# IOX16_v22.net
KiCad netlist of a schematic drawn in EAGLE
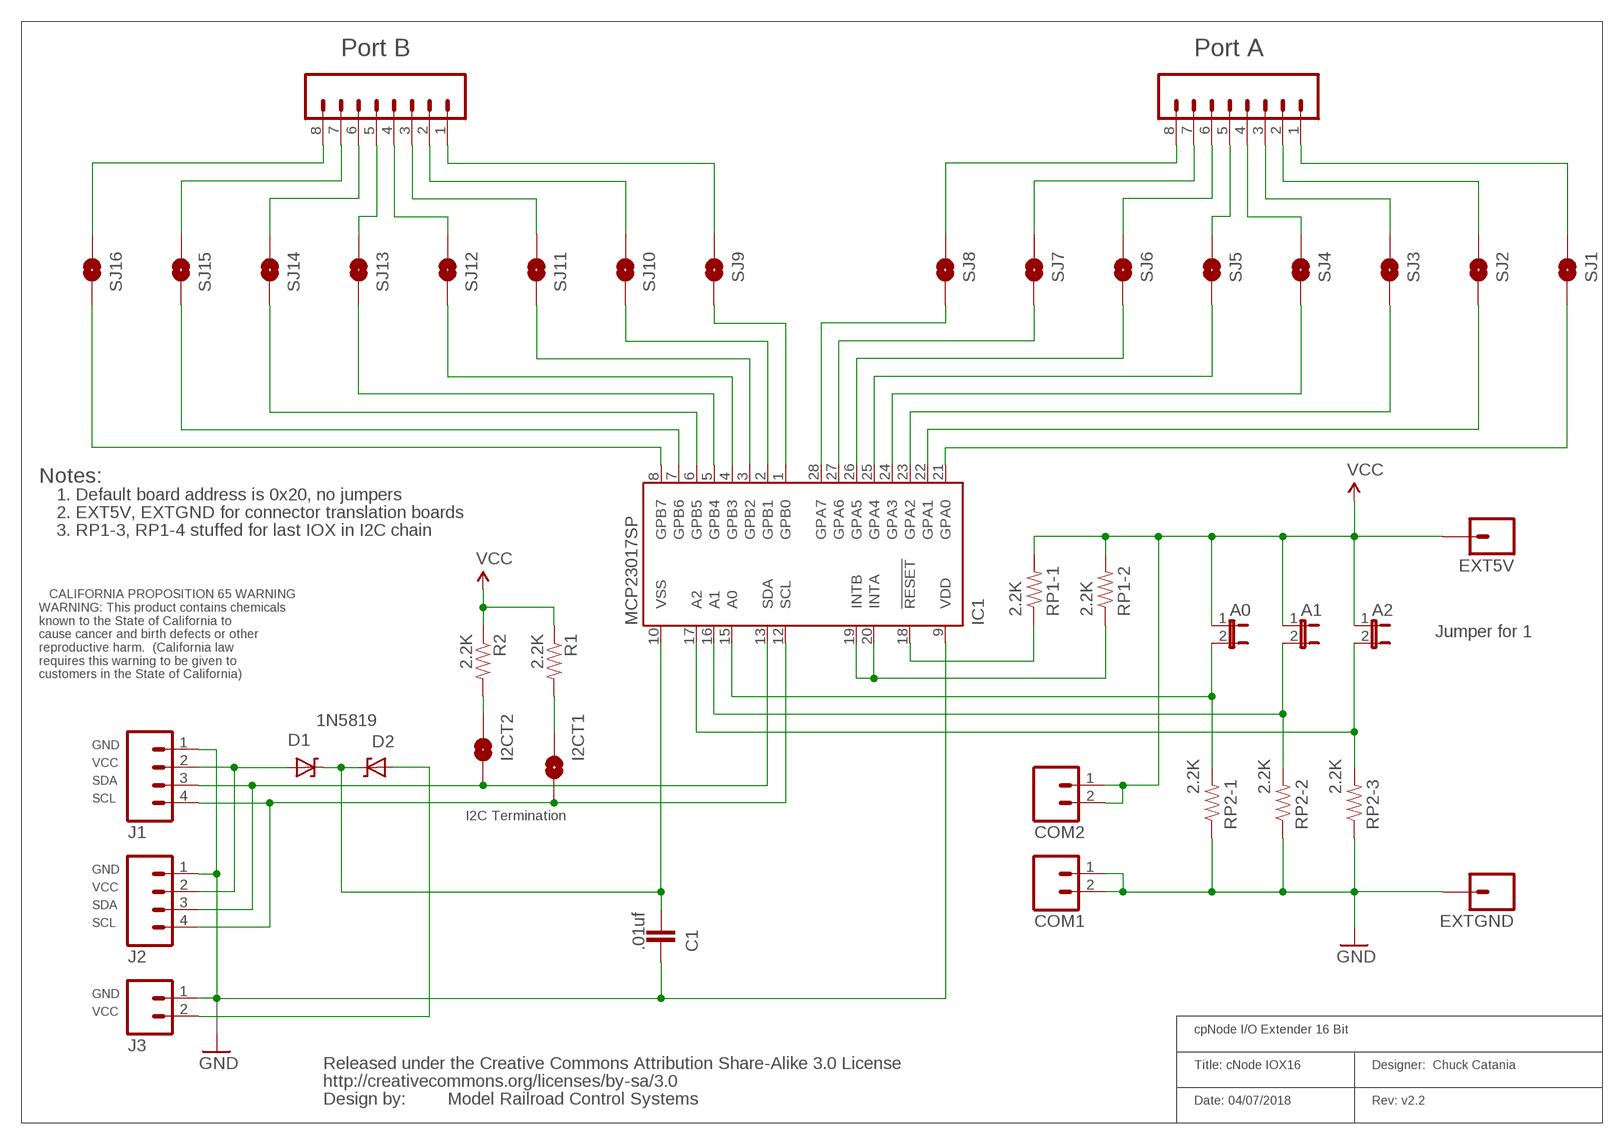
[diagram p0: schematic, sheet 1]

(export (version "E")
  (design (tool "Eeschema 10.0.6"))
  (components
    (comp (ref "A0")
      (value "JUMPER-2PTH")
      (footprint "eagle-import:1X02")
      (libsource (lib "eagle-import") (part "JUMPER-2PTH"))
    )
    (comp (ref "A1")
      (value "JUMPER-2PTH")
      (footprint "eagle-import:1X02")
      (libsource (lib "eagle-import") (part "JUMPER-2PTH"))
    )
    (comp (ref "A2")
      (value "JUMPER-2PTH")
      (footprint "eagle-import:1X02")
      (libsource (lib "eagle-import") (part "JUMPER-2PTH"))
    )
    (comp (ref "C1")
      (value ".01uf")
      (footprint "eagle-import:AXIAL-5MM")
      (libsource (lib "eagle-import") (part "CAP_"))
    )
    (comp (ref "COM1")
      (value "M021X02_NO_SILK")
      (footprint "eagle-import:1X02_NO_SILK")
      (libsource (lib "eagle-import") (part "M021X02_NO_SILK"))
    )
    (comp (ref "COM2")
      (value "M021X02_NO_SILK")
      (footprint "eagle-import:1X02_NO_SILK")
      (libsource (lib "eagle-import") (part "M021X02_NO_SILK"))
    )
    (comp (ref "D1")
      (value "DIODE-ZENERPTH")
      (footprint "eagle-import:DIODE-ZENER")
      (libsource (lib "eagle-import") (part "DIODE-ZENERPTH"))
    )
    (comp (ref "D2")
      (value "DIODE-ZENERPTH")
      (footprint "eagle-import:DIODE-ZENER")
      (libsource (lib "eagle-import") (part "DIODE-ZENERPTH"))
    )
    (comp (ref "EXT5V")
      (value "M01PTH_LONGPAD")
      (footprint "eagle-import:1X01_LONGPAD")
      (libsource (lib "eagle-import") (part "M01PTH_LONGPAD"))
    )
    (comp (ref "EXTGND")
      (value "M01PTH_LONGPAD")
      (footprint "eagle-import:1X01_LONGPAD")
      (libsource (lib "eagle-import") (part "M01PTH_LONGPAD"))
    )
    (comp (ref "I2CT1")
      (value "PAD-SOLDERJUMPERNC")
      (footprint "eagle-import:2P-SMD-2X3.3")
      (libsource (lib "eagle-import") (part "PAD-SOLDERJUMPERNC"))
    )
    (comp (ref "I2CT2")
      (value "PAD-SOLDERJUMPERNC")
      (footprint "eagle-import:2P-SMD-2X3.3")
      (libsource (lib "eagle-import") (part "PAD-SOLDERJUMPERNC"))
    )
    (comp (ref "IC1")
      (value "MCP23017SP")
      (footprint "eagle-import:DIL28-3")
      (fields (field (name "MF") "MICROCHIP") (field (name "MPN") "MCP23017-E/SP"))
      (libsource (lib "eagle-import") (part "MCP23017SP"))
    )
    (comp (ref "J1")
      (value "M04PTH")
      (footprint "eagle-import:1X04")
      (libsource (lib "eagle-import") (part "M04PTH"))
    )
    (comp (ref "J2")
      (value "M04PTH")
      (footprint "eagle-import:1X04")
      (libsource (lib "eagle-import") (part "M04PTH"))
    )
    (comp (ref "J3")
      (value "M021X02_NO_SILK")
      (footprint "eagle-import:1X02_NO_SILK")
      (libsource (lib "eagle-import") (part "M021X02_NO_SILK"))
    )
    (comp (ref "PORTA")
      (value "M081X08")
      (footprint "eagle-import:1X08")
      (libsource (lib "eagle-import") (part "M081X08"))
    )
    (comp (ref "PORTB")
      (value "M081X08")
      (footprint "eagle-import:1X08")
      (libsource (lib "eagle-import") (part "M081X08"))
    )
    (comp (ref "R1")
      (value "2.2K")
      (footprint "eagle-import:AXIAL-0.4")
      (libsource (lib "eagle-import") (part "RESISTORPTH-1/4W"))
    )
    (comp (ref "R2")
      (value "2.2K")
      (footprint "eagle-import:AXIAL-0.4")
      (libsource (lib "eagle-import") (part "RESISTORPTH-1/4W"))
    )
    (comp (ref "RP1-1")
      (value "2.2K")
      (footprint "eagle-import:AXIAL-0.4")
      (libsource (lib "eagle-import") (part "RESISTORPTH-1/4W"))
    )
    (comp (ref "RP1-2")
      (value "2.2K")
      (footprint "eagle-import:AXIAL-0.4")
      (libsource (lib "eagle-import") (part "RESISTORPTH-1/4W"))
    )
    (comp (ref "RP2-1")
      (value "2.2K")
      (footprint "eagle-import:AXIAL-0.4")
      (libsource (lib "eagle-import") (part "RESISTORPTH-1/4W"))
    )
    (comp (ref "RP2-2")
      (value "2.2K")
      (footprint "eagle-import:AXIAL-0.4")
      (libsource (lib "eagle-import") (part "RESISTORPTH-1/4W"))
    )
    (comp (ref "RP2-3")
      (value "2.2K")
      (footprint "eagle-import:AXIAL-0.4")
      (libsource (lib "eagle-import") (part "RESISTORPTH-1/4W"))
    )
    (comp (ref "SJ1")
      (value "PAD-SOLDERJUMPERNC")
      (footprint "eagle-import:2P-SMD-2X3.3")
      (libsource (lib "eagle-import") (part "PAD-SOLDERJUMPERNC"))
    )
    (comp (ref "SJ2")
      (value "PAD-SOLDERJUMPERNC")
      (footprint "eagle-import:2P-SMD-2X3.3")
      (libsource (lib "eagle-import") (part "PAD-SOLDERJUMPERNC"))
    )
    (comp (ref "SJ3")
      (value "PAD-SOLDERJUMPERNC")
      (footprint "eagle-import:2P-SMD-2X3.3")
      (libsource (lib "eagle-import") (part "PAD-SOLDERJUMPERNC"))
    )
    (comp (ref "SJ4")
      (value "PAD-SOLDERJUMPERNC")
      (footprint "eagle-import:2P-SMD-2X3.3")
      (libsource (lib "eagle-import") (part "PAD-SOLDERJUMPERNC"))
    )
    (comp (ref "SJ5")
      (value "PAD-SOLDERJUMPERNC")
      (footprint "eagle-import:2P-SMD-2X3.3")
      (libsource (lib "eagle-import") (part "PAD-SOLDERJUMPERNC"))
    )
    (comp (ref "SJ6")
      (value "PAD-SOLDERJUMPERNC")
      (footprint "eagle-import:2P-SMD-2X3.3")
      (libsource (lib "eagle-import") (part "PAD-SOLDERJUMPERNC"))
    )
    (comp (ref "SJ7")
      (value "PAD-SOLDERJUMPERNC")
      (footprint "eagle-import:2P-SMD-2X3.3")
      (libsource (lib "eagle-import") (part "PAD-SOLDERJUMPERNC"))
    )
    (comp (ref "SJ8")
      (value "PAD-SOLDERJUMPERNC")
      (footprint "eagle-import:2P-SMD-2X3.3")
      (libsource (lib "eagle-import") (part "PAD-SOLDERJUMPERNC"))
    )
    (comp (ref "SJ9")
      (value "PAD-SOLDERJUMPERNC")
      (footprint "eagle-import:2P-SMD-2X3.3")
      (libsource (lib "eagle-import") (part "PAD-SOLDERJUMPERNC"))
    )
    (comp (ref "SJ10")
      (value "PAD-SOLDERJUMPERNC")
      (footprint "eagle-import:2P-SMD-2X3.3")
      (libsource (lib "eagle-import") (part "PAD-SOLDERJUMPERNC"))
    )
    (comp (ref "SJ11")
      (value "PAD-SOLDERJUMPERNC")
      (footprint "eagle-import:2P-SMD-2X3.3")
      (libsource (lib "eagle-import") (part "PAD-SOLDERJUMPERNC"))
    )
    (comp (ref "SJ12")
      (value "PAD-SOLDERJUMPERNC")
      (footprint "eagle-import:2P-SMD-2X3.3")
      (libsource (lib "eagle-import") (part "PAD-SOLDERJUMPERNC"))
    )
    (comp (ref "SJ13")
      (value "PAD-SOLDERJUMPERNC")
      (footprint "eagle-import:2P-SMD-2X3.3")
      (libsource (lib "eagle-import") (part "PAD-SOLDERJUMPERNC"))
    )
    (comp (ref "SJ14")
      (value "PAD-SOLDERJUMPERNC")
      (footprint "eagle-import:2P-SMD-2X3.3")
      (libsource (lib "eagle-import") (part "PAD-SOLDERJUMPERNC"))
    )
    (comp (ref "SJ15")
      (value "PAD-SOLDERJUMPERNC")
      (footprint "eagle-import:2P-SMD-2X3.3")
      (libsource (lib "eagle-import") (part "PAD-SOLDERJUMPERNC"))
    )
    (comp (ref "SJ16")
      (value "PAD-SOLDERJUMPERNC")
      (footprint "eagle-import:2P-SMD-2X3.3")
      (libsource (lib "eagle-import") (part "PAD-SOLDERJUMPERNC"))
    )
    (comp (ref "U$1")
      (value "CREATIVE_COMMONS")
      (footprint "eagle-import:CREATIVE_COMMONS")
      (libsource (lib "eagle-import") (part "CREATIVE_COMMONS"))
    )
    (comp (ref "U$2")
      (value "CA-PROP65WARNING")
      (footprint "eagle-import:CA-PROP65WARNING")
      (libsource (lib "eagle-import") (part "CA-PROP65WARNING"))
    )
  )
  (nets
    (net (code "1") (name "GND") (class "Default")
      (node (ref "COM1") (pin "1") (pinfunction "1_1") (pintype "passive"))
      (node (ref "COM1") (pin "2") (pinfunction "2_2") (pintype "passive"))
      (node (ref "EXTGND") (pin "1") (pinfunction "1_1") (pintype "passive"))
      (node (ref "RP2-1") (pin "P$1") (pinfunction "1_P$1") (pintype "passive"))
      (node (ref "RP2-2") (pin "P$1") (pinfunction "1_P$1") (pintype "passive"))
      (node (ref "RP2-3") (pin "P$1") (pinfunction "1_P$1") (pintype "passive"))
    )
    (net (code "2") (name "Net-(C1-1)") (class "Default")
      (node (ref "C1") (pin "P$1") (pinfunction "1_P$1") (pintype "passive"))
      (node (ref "IC1") (pin "9") (pinfunction "VDD_9") (pintype "power_in"))
      (node (ref "J1") (pin "1") (pinfunction "1_1") (pintype "passive"))
      (node (ref "J2") (pin "1") (pinfunction "1_1") (pintype "passive"))
      (node (ref "J3") (pin "1") (pinfunction "1_1") (pintype "passive"))
    )
    (net (code "3") (name "Net-(C1-2)") (class "Default")
      (node (ref "C1") (pin "P$2") (pinfunction "2_P$2") (pintype "passive"))
      (node (ref "D1") (pin "P$1") (pinfunction "C_P$1") (pintype "passive"))
      (node (ref "D2") (pin "P$1") (pinfunction "C_P$1") (pintype "passive"))
      (node (ref "IC1") (pin "10") (pinfunction "VSS_10") (pintype "power_in"))
    )
    (net (code "4") (name "Net-(D1-A)") (class "Default")
      (node (ref "D1") (pin "P$2") (pinfunction "A_P$2") (pintype "passive"))
      (node (ref "J1") (pin "2") (pinfunction "2_2") (pintype "passive"))
      (node (ref "J2") (pin "2") (pinfunction "2_2") (pintype "passive"))
    )
    (net (code "5") (name "Net-(D2-A)") (class "Default")
      (node (ref "D2") (pin "P$2") (pinfunction "A_P$2") (pintype "passive"))
      (node (ref "J3") (pin "2") (pinfunction "2_2") (pintype "passive"))
    )
    (net (code "6") (name "Net-(IC1-A0)") (class "Default")
      (node (ref "A0") (pin "2") (pinfunction "2_2") (pintype "passive"))
      (node (ref "IC1") (pin "15") (pinfunction "A0_15") (pintype "input"))
      (node (ref "RP2-1") (pin "P$2") (pinfunction "2_P$2") (pintype "passive"))
    )
    (net (code "7") (name "Net-(IC1-A1)") (class "Default")
      (node (ref "A1") (pin "2") (pinfunction "2_2") (pintype "passive"))
      (node (ref "IC1") (pin "16") (pinfunction "A1_16") (pintype "input"))
      (node (ref "RP2-2") (pin "P$2") (pinfunction "2_P$2") (pintype "passive"))
    )
    (net (code "8") (name "Net-(IC1-A2)") (class "Default")
      (node (ref "A2") (pin "2") (pinfunction "2_2") (pintype "passive"))
      (node (ref "IC1") (pin "17") (pinfunction "A2_17") (pintype "input"))
      (node (ref "RP2-3") (pin "P$2") (pinfunction "2_P$2") (pintype "passive"))
    )
    (net (code "9") (name "Net-(IC1-GPA0)") (class "Default")
      (node (ref "IC1") (pin "21") (pinfunction "GPA0_21") (pintype "bidirectional"))
      (node (ref "SJ1") (pin "2") (pinfunction "2_2") (pintype "passive"))
    )
    (net (code "10") (name "Net-(IC1-GPA1)") (class "Default")
      (node (ref "IC1") (pin "22") (pinfunction "GPA1_22") (pintype "bidirectional"))
      (node (ref "SJ2") (pin "2") (pinfunction "2_2") (pintype "passive"))
    )
    (net (code "11") (name "Net-(IC1-GPA2)") (class "Default")
      (node (ref "IC1") (pin "23") (pinfunction "GPA2_23") (pintype "bidirectional"))
      (node (ref "SJ3") (pin "2") (pinfunction "2_2") (pintype "passive"))
    )
    (net (code "12") (name "Net-(IC1-GPA3)") (class "Default")
      (node (ref "IC1") (pin "24") (pinfunction "GPA3_24") (pintype "bidirectional"))
      (node (ref "SJ4") (pin "2") (pinfunction "2_2") (pintype "passive"))
    )
    (net (code "13") (name "Net-(IC1-GPA4)") (class "Default")
      (node (ref "IC1") (pin "25") (pinfunction "GPA4_25") (pintype "bidirectional"))
      (node (ref "SJ5") (pin "2") (pinfunction "2_2") (pintype "passive"))
    )
    (net (code "14") (name "Net-(IC1-GPA5)") (class "Default")
      (node (ref "IC1") (pin "26") (pinfunction "GPA5_26") (pintype "bidirectional"))
      (node (ref "SJ6") (pin "2") (pinfunction "2_2") (pintype "passive"))
    )
    (net (code "15") (name "Net-(IC1-GPA6)") (class "Default")
      (node (ref "IC1") (pin "27") (pinfunction "GPA6_27") (pintype "bidirectional"))
      (node (ref "SJ7") (pin "2") (pinfunction "2_2") (pintype "passive"))
    )
    (net (code "16") (name "Net-(IC1-GPA7)") (class "Default")
      (node (ref "IC1") (pin "28") (pinfunction "GPA7_28") (pintype "bidirectional"))
      (node (ref "SJ8") (pin "2") (pinfunction "2_2") (pintype "passive"))
    )
    (net (code "17") (name "Net-(IC1-GPB0)") (class "Default")
      (node (ref "IC1") (pin "1") (pinfunction "GPB0_1") (pintype "bidirectional"))
      (node (ref "SJ9") (pin "2") (pinfunction "2_2") (pintype "passive"))
    )
    (net (code "18") (name "Net-(IC1-GPB1)") (class "Default")
      (node (ref "IC1") (pin "2") (pinfunction "GPB1_2") (pintype "bidirectional"))
      (node (ref "SJ10") (pin "2") (pinfunction "2_2") (pintype "passive"))
    )
    (net (code "19") (name "Net-(IC1-GPB2)") (class "Default")
      (node (ref "IC1") (pin "3") (pinfunction "GPB2_3") (pintype "bidirectional"))
      (node (ref "SJ11") (pin "2") (pinfunction "2_2") (pintype "passive"))
    )
    (net (code "20") (name "Net-(IC1-GPB3)") (class "Default")
      (node (ref "IC1") (pin "4") (pinfunction "GPB3_4") (pintype "bidirectional"))
      (node (ref "SJ12") (pin "2") (pinfunction "2_2") (pintype "passive"))
    )
    (net (code "21") (name "Net-(IC1-GPB4)") (class "Default")
      (node (ref "IC1") (pin "5") (pinfunction "GPB4_5") (pintype "bidirectional"))
      (node (ref "SJ13") (pin "2") (pinfunction "2_2") (pintype "passive"))
    )
    (net (code "22") (name "Net-(IC1-GPB5)") (class "Default")
      (node (ref "IC1") (pin "6") (pinfunction "GPB5_6") (pintype "bidirectional"))
      (node (ref "SJ14") (pin "2") (pinfunction "2_2") (pintype "passive"))
    )
    (net (code "23") (name "Net-(IC1-GPB6)") (class "Default")
      (node (ref "IC1") (pin "7") (pinfunction "GPB6_7") (pintype "bidirectional"))
      (node (ref "SJ15") (pin "2") (pinfunction "2_2") (pintype "passive"))
    )
    (net (code "24") (name "Net-(IC1-GPB7)") (class "Default")
      (node (ref "IC1") (pin "8") (pinfunction "GPB7_8") (pintype "bidirectional"))
      (node (ref "SJ16") (pin "2") (pinfunction "2_2") (pintype "passive"))
    )
    (net (code "25") (name "Net-(IC1-INTA)") (class "Default")
      (node (ref "IC1") (pin "19") (pinfunction "INTB_19") (pintype "output"))
      (node (ref "IC1") (pin "20") (pinfunction "INTA_20") (pintype "output"))
      (node (ref "RP1-2") (pin "P$1") (pinfunction "1_P$1") (pintype "passive"))
    )
    (net (code "26") (name "Net-(IC1-SCL)") (class "Default")
      (node (ref "I2CT1") (pin "2") (pinfunction "2_2") (pintype "passive"))
      (node (ref "IC1") (pin "12") (pinfunction "SCL_12") (pintype "input"))
      (node (ref "J1") (pin "4") (pinfunction "4_4") (pintype "passive"))
      (node (ref "J2") (pin "4") (pinfunction "4_4") (pintype "passive"))
    )
    (net (code "27") (name "Net-(IC1-SDA)") (class "Default")
      (node (ref "I2CT2") (pin "2") (pinfunction "2_2") (pintype "passive"))
      (node (ref "IC1") (pin "13") (pinfunction "SDA_13") (pintype "bidirectional"))
      (node (ref "J1") (pin "3") (pinfunction "3_3") (pintype "passive"))
      (node (ref "J2") (pin "3") (pinfunction "3_3") (pintype "passive"))
    )
    (net (code "28") (name "Net-(IC1-~{RESET})") (class "Default")
      (node (ref "IC1") (pin "18") (pinfunction "~{RESET}_18") (pintype "input"))
      (node (ref "RP1-1") (pin "P$1") (pinfunction "1_P$1") (pintype "passive"))
    )
    (net (code "29") (name "Net-(PORTA-Pad1)") (class "Default")
      (node (ref "PORTA") (pin "1") (pinfunction "1_1") (pintype "passive"))
      (node (ref "SJ1") (pin "1") (pinfunction "1_1") (pintype "passive"))
    )
    (net (code "30") (name "Net-(PORTA-Pad2)") (class "Default")
      (node (ref "PORTA") (pin "2") (pinfunction "2_2") (pintype "passive"))
      (node (ref "SJ2") (pin "1") (pinfunction "1_1") (pintype "passive"))
    )
    (net (code "31") (name "Net-(PORTA-Pad3)") (class "Default")
      (node (ref "PORTA") (pin "3") (pinfunction "3_3") (pintype "passive"))
      (node (ref "SJ3") (pin "1") (pinfunction "1_1") (pintype "passive"))
    )
    (net (code "32") (name "Net-(PORTA-Pad4)") (class "Default")
      (node (ref "PORTA") (pin "4") (pinfunction "4_4") (pintype "passive"))
      (node (ref "SJ4") (pin "1") (pinfunction "1_1") (pintype "passive"))
    )
    (net (code "33") (name "Net-(PORTA-Pad5)") (class "Default")
      (node (ref "PORTA") (pin "5") (pinfunction "5_5") (pintype "passive"))
      (node (ref "SJ5") (pin "1") (pinfunction "1_1") (pintype "passive"))
    )
    (net (code "34") (name "Net-(PORTA-Pad6)") (class "Default")
      (node (ref "PORTA") (pin "6") (pinfunction "6_6") (pintype "passive"))
      (node (ref "SJ6") (pin "1") (pinfunction "1_1") (pintype "passive"))
    )
    (net (code "35") (name "Net-(PORTA-Pad7)") (class "Default")
      (node (ref "PORTA") (pin "7") (pinfunction "7_7") (pintype "passive"))
      (node (ref "SJ7") (pin "1") (pinfunction "1_1") (pintype "passive"))
    )
    (net (code "36") (name "Net-(PORTA-Pad8)") (class "Default")
      (node (ref "PORTA") (pin "8") (pinfunction "8_8") (pintype "passive"))
      (node (ref "SJ8") (pin "1") (pinfunction "1_1") (pintype "passive"))
    )
    (net (code "37") (name "Net-(PORTB-Pad1)") (class "Default")
      (node (ref "PORTB") (pin "1") (pinfunction "1_1") (pintype "passive"))
      (node (ref "SJ9") (pin "1") (pinfunction "1_1") (pintype "passive"))
    )
    (net (code "38") (name "Net-(PORTB-Pad2)") (class "Default")
      (node (ref "PORTB") (pin "2") (pinfunction "2_2") (pintype "passive"))
      (node (ref "SJ10") (pin "1") (pinfunction "1_1") (pintype "passive"))
    )
    (net (code "39") (name "Net-(PORTB-Pad3)") (class "Default")
      (node (ref "PORTB") (pin "3") (pinfunction "3_3") (pintype "passive"))
      (node (ref "SJ11") (pin "1") (pinfunction "1_1") (pintype "passive"))
    )
    (net (code "40") (name "Net-(PORTB-Pad4)") (class "Default")
      (node (ref "PORTB") (pin "4") (pinfunction "4_4") (pintype "passive"))
      (node (ref "SJ12") (pin "1") (pinfunction "1_1") (pintype "passive"))
    )
    (net (code "41") (name "Net-(PORTB-Pad5)") (class "Default")
      (node (ref "PORTB") (pin "5") (pinfunction "5_5") (pintype "passive"))
      (node (ref "SJ13") (pin "1") (pinfunction "1_1") (pintype "passive"))
    )
    (net (code "42") (name "Net-(PORTB-Pad6)") (class "Default")
      (node (ref "PORTB") (pin "6") (pinfunction "6_6") (pintype "passive"))
      (node (ref "SJ14") (pin "1") (pinfunction "1_1") (pintype "passive"))
    )
    (net (code "43") (name "Net-(PORTB-Pad7)") (class "Default")
      (node (ref "PORTB") (pin "7") (pinfunction "7_7") (pintype "passive"))
      (node (ref "SJ15") (pin "1") (pinfunction "1_1") (pintype "passive"))
    )
    (net (code "44") (name "Net-(PORTB-Pad8)") (class "Default")
      (node (ref "PORTB") (pin "8") (pinfunction "8_8") (pintype "passive"))
      (node (ref "SJ16") (pin "1") (pinfunction "1_1") (pintype "passive"))
    )
    (net (code "45") (name "Net-(R1-2)") (class "Default")
      (node (ref "I2CT1") (pin "1") (pinfunction "1_1") (pintype "passive"))
      (node (ref "R1") (pin "P$2") (pinfunction "2_P$2") (pintype "passive"))
    )
    (net (code "46") (name "Net-(R2-2)") (class "Default")
      (node (ref "I2CT2") (pin "1") (pinfunction "1_1") (pintype "passive"))
      (node (ref "R2") (pin "P$2") (pinfunction "2_P$2") (pintype "passive"))
    )
    (net (code "47") (name "VCC") (class "Default")
      (node (ref "A0") (pin "1") (pinfunction "1_1") (pintype "passive"))
      (node (ref "A1") (pin "1") (pinfunction "1_1") (pintype "passive"))
      (node (ref "A2") (pin "1") (pinfunction "1_1") (pintype "passive"))
      (node (ref "COM2") (pin "1") (pinfunction "1_1") (pintype "passive"))
      (node (ref "COM2") (pin "2") (pinfunction "2_2") (pintype "passive"))
      (node (ref "EXT5V") (pin "1") (pinfunction "1_1") (pintype "passive"))
      (node (ref "R1") (pin "P$1") (pinfunction "1_P$1") (pintype "passive"))
      (node (ref "R2") (pin "P$1") (pinfunction "1_P$1") (pintype "passive"))
      (node (ref "RP1-1") (pin "P$2") (pinfunction "2_P$2") (pintype "passive"))
      (node (ref "RP1-2") (pin "P$2") (pinfunction "2_P$2") (pintype "passive"))
    )
  )
)
